# ESC.net
KiCad netlist of a schematic drawn in Altium Designer
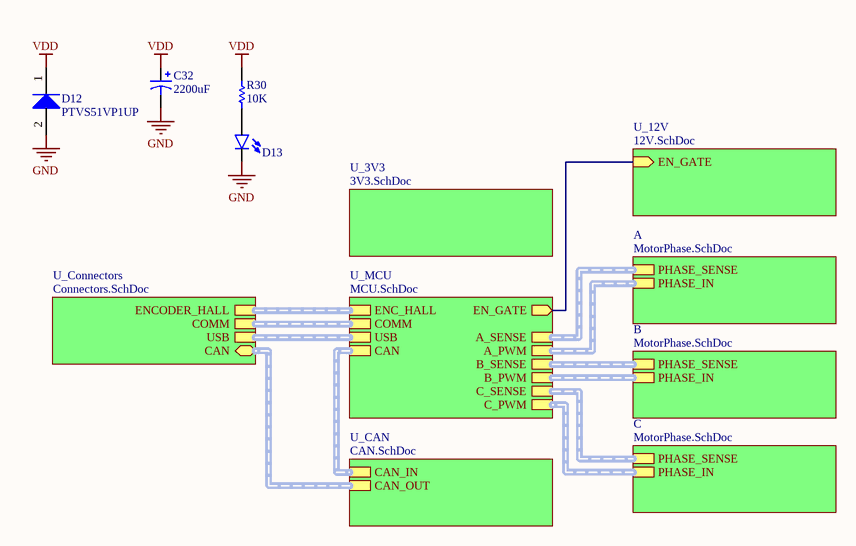
[diagram p0: ESC.SchDoc]

(export (version "E")
  (design (tool "Eeschema 10.0.6"))
  (components
    (comp (ref "C32")
      (value "2200uF")
      (footprint "CAP-RADIAL-HORZ [18x35.5]")
      (fields
        (field (name "PARTNUMBER") "UVR1J222MHD")
        (field (name "VOLTAGE") "63V")
        (field (name "TOLERANCE") "20%")
      )
      (libsource (lib "Components") (part "CAP 2200uF"))
    )
    (comp (ref "D12")
      (value "PTVS51VP1UP")
      (footprint "SOD-128")
      (fields (field (name "PARTNUMBER") "PTVS51VP1UP,115") (field (name "MANUFACTURER") "NXP"))
      (libsource (lib "Diodes") (part "PTVS51VP1UP,115"))
    )
    (comp (ref "D13")
      (value "LED-BLUE")
      (footprint "LED0603")
      (fields (field (name "PARTNUMBER") "LTST-C193TBKT-5A") (field (name "MANUFACTURER") "Lite-On Inc."))
      (libsource (lib "LEDs") (part "LED_0603_BLUE_5mA"))
    )
    (comp (ref "R30")
      (value "10K")
      (footprint "R0603[1608]")
      (description "10K 0.25W 1% 0603 (1005 Metric)")
      (fields (field (name "TOLERANCE") "1%") (field (name "POWER") "0.25W"))
      (libsource (lib "Resistors") (part "RES_10K_0603_1%"))
    )
  )
  (nets
    (net (code "13") (name "GND") (class "Default")
      (node (ref "C32") (pin "2") (pinfunction "2_2") (pintype "passive"))
      (node (ref "D12") (pin "2") (pinfunction "A_2") (pintype "passive"))
      (node (ref "D13") (pin "C") (pinfunction "C_C") (pintype "passive"))
    )
    (net (code "14") (name "Net-(D13-PadA)") (class "Default")
      (node (ref "D13") (pin "A") (pinfunction "A_A") (pintype "passive"))
      (node (ref "R30") (pin "1") (pinfunction "1_1") (pintype "passive"))
    )
    (net (code "15") (name "VDD") (class "Default")
      (node (ref "C32") (pin "1") (pinfunction "1_1") (pintype "passive"))
      (node (ref "D12") (pin "1") (pinfunction "K_1") (pintype "passive"))
      (node (ref "R30") (pin "2") (pinfunction "2_2") (pintype "passive"))
    )
  )
)
